# buttonboard.net
KiCad netlist of a schematic drawn in Altium Designer
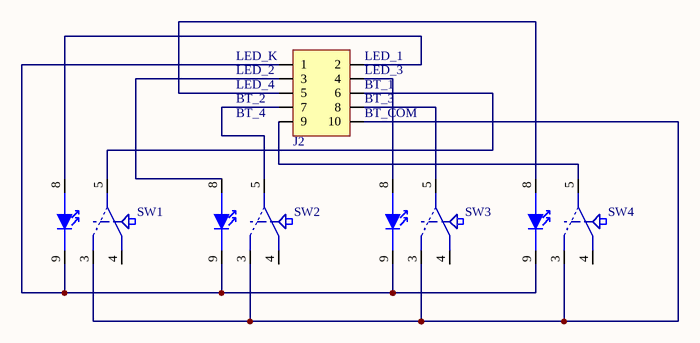
[diagram p0: buttonboard.SchDoc]

(export (version "E")
  (design (tool "Eeschema 10.0.6"))
  (components
    (comp (ref "J2")
      (value "Wannenstecker 10pol 2,54mm")
      (footprint "WSL10G")
      (libsource (lib "wannenstecker") (part "Wannenstecker 10pol 2,54mm"))
    )
    (comp (ref "SW1")
      (value "ITT_SER")
      (footprint "ITT_SER")
      (description "Digitaster LED")
      (libsource (lib "switch_relais") (part "ITT_SER"))
    )
    (comp (ref "SW2")
      (value "ITT_SER")
      (footprint "ITT_SER")
      (description "Digitaster LED")
      (libsource (lib "switch_relais") (part "ITT_SER"))
    )
    (comp (ref "SW3")
      (value "ITT_SER")
      (footprint "ITT_SER")
      (description "Digitaster LED")
      (libsource (lib "switch_relais") (part "ITT_SER"))
    )
    (comp (ref "SW4")
      (value "ITT_SER")
      (footprint "ITT_SER")
      (description "Digitaster LED")
      (libsource (lib "switch_relais") (part "ITT_SER"))
    )
  )
  (nets
    (net (code "1") (name "Net-(J2-Pad1)") (class "Default")
      (node (ref "J2") (pin "1") (pinfunction "1_1") (pintype "passive"))
      (node (ref "SW1") (pin "9") (pinfunction "1_9") (pintype "passive"))
      (node (ref "SW2") (pin "9") (pinfunction "1_9") (pintype "passive"))
      (node (ref "SW3") (pin "9") (pinfunction "1_9") (pintype "passive"))
      (node (ref "SW4") (pin "9") (pinfunction "1_9") (pintype "passive"))
    )
    (net (code "2") (name "Net-(J2-Pad2)") (class "Default")
      (node (ref "J2") (pin "2") (pinfunction "2_2") (pintype "passive"))
      (node (ref "SW1") (pin "8") (pinfunction "2_8") (pintype "passive"))
    )
    (net (code "3") (name "Net-(J2-Pad3)") (class "Default")
      (node (ref "J2") (pin "3") (pinfunction "3_3") (pintype "passive"))
      (node (ref "SW2") (pin "8") (pinfunction "2_8") (pintype "passive"))
    )
    (net (code "4") (name "Net-(J2-Pad4)") (class "Default")
      (node (ref "J2") (pin "4") (pinfunction "4_4") (pintype "passive"))
      (node (ref "SW3") (pin "8") (pinfunction "2_8") (pintype "passive"))
    )
    (net (code "5") (name "Net-(J2-Pad5)") (class "Default")
      (node (ref "J2") (pin "5") (pinfunction "5_5") (pintype "passive"))
      (node (ref "SW4") (pin "8") (pinfunction "2_8") (pintype "passive"))
    )
    (net (code "6") (name "Net-(J2-Pad6)") (class "Default")
      (node (ref "J2") (pin "6") (pinfunction "6_6") (pintype "passive"))
      (node (ref "SW1") (pin "5") (pinfunction "1_5") (pintype "passive"))
    )
    (net (code "7") (name "Net-(J2-Pad7)") (class "Default")
      (node (ref "J2") (pin "7") (pinfunction "7_7") (pintype "passive"))
      (node (ref "SW2") (pin "5") (pinfunction "1_5") (pintype "passive"))
    )
    (net (code "8") (name "Net-(J2-Pad8)") (class "Default")
      (node (ref "J2") (pin "8") (pinfunction "8_8") (pintype "passive"))
      (node (ref "SW3") (pin "5") (pinfunction "1_5") (pintype "passive"))
    )
    (net (code "9") (name "Net-(J2-Pad9)") (class "Default")
      (node (ref "J2") (pin "9") (pinfunction "9_9") (pintype "passive"))
      (node (ref "SW4") (pin "5") (pinfunction "1_5") (pintype "passive"))
    )
    (net (code "10") (name "Net-(J2-Pad10)") (class "Default")
      (node (ref "J2") (pin "10") (pinfunction "10_10") (pintype "passive"))
      (node (ref "SW1") (pin "3") (pinfunction "3_3") (pintype "passive"))
      (node (ref "SW2") (pin "3") (pinfunction "3_3") (pintype "passive"))
      (node (ref "SW3") (pin "3") (pinfunction "3_3") (pintype "passive"))
      (node (ref "SW4") (pin "3") (pinfunction "3_3") (pintype "passive"))
    )
    (net (code "11") (name "unconnected-(SW1-2-Pad4)") (class "Default")
      (node (ref "SW1") (pin "4") (pinfunction "2_4") (pintype "passive"))
    )
    (net (code "12") (name "unconnected-(SW2-2-Pad4)") (class "Default")
      (node (ref "SW2") (pin "4") (pinfunction "2_4") (pintype "passive"))
    )
    (net (code "13") (name "unconnected-(SW3-2-Pad4)") (class "Default")
      (node (ref "SW3") (pin "4") (pinfunction "2_4") (pintype "passive"))
    )
    (net (code "14") (name "unconnected-(SW4-2-Pad4)") (class "Default")
      (node (ref "SW4") (pin "4") (pinfunction "2_4") (pintype "passive"))
    )
  )
)
